# Mach_dieu_khien_tu_xa.net
KiCad netlist of a schematic drawn in Altium Designer
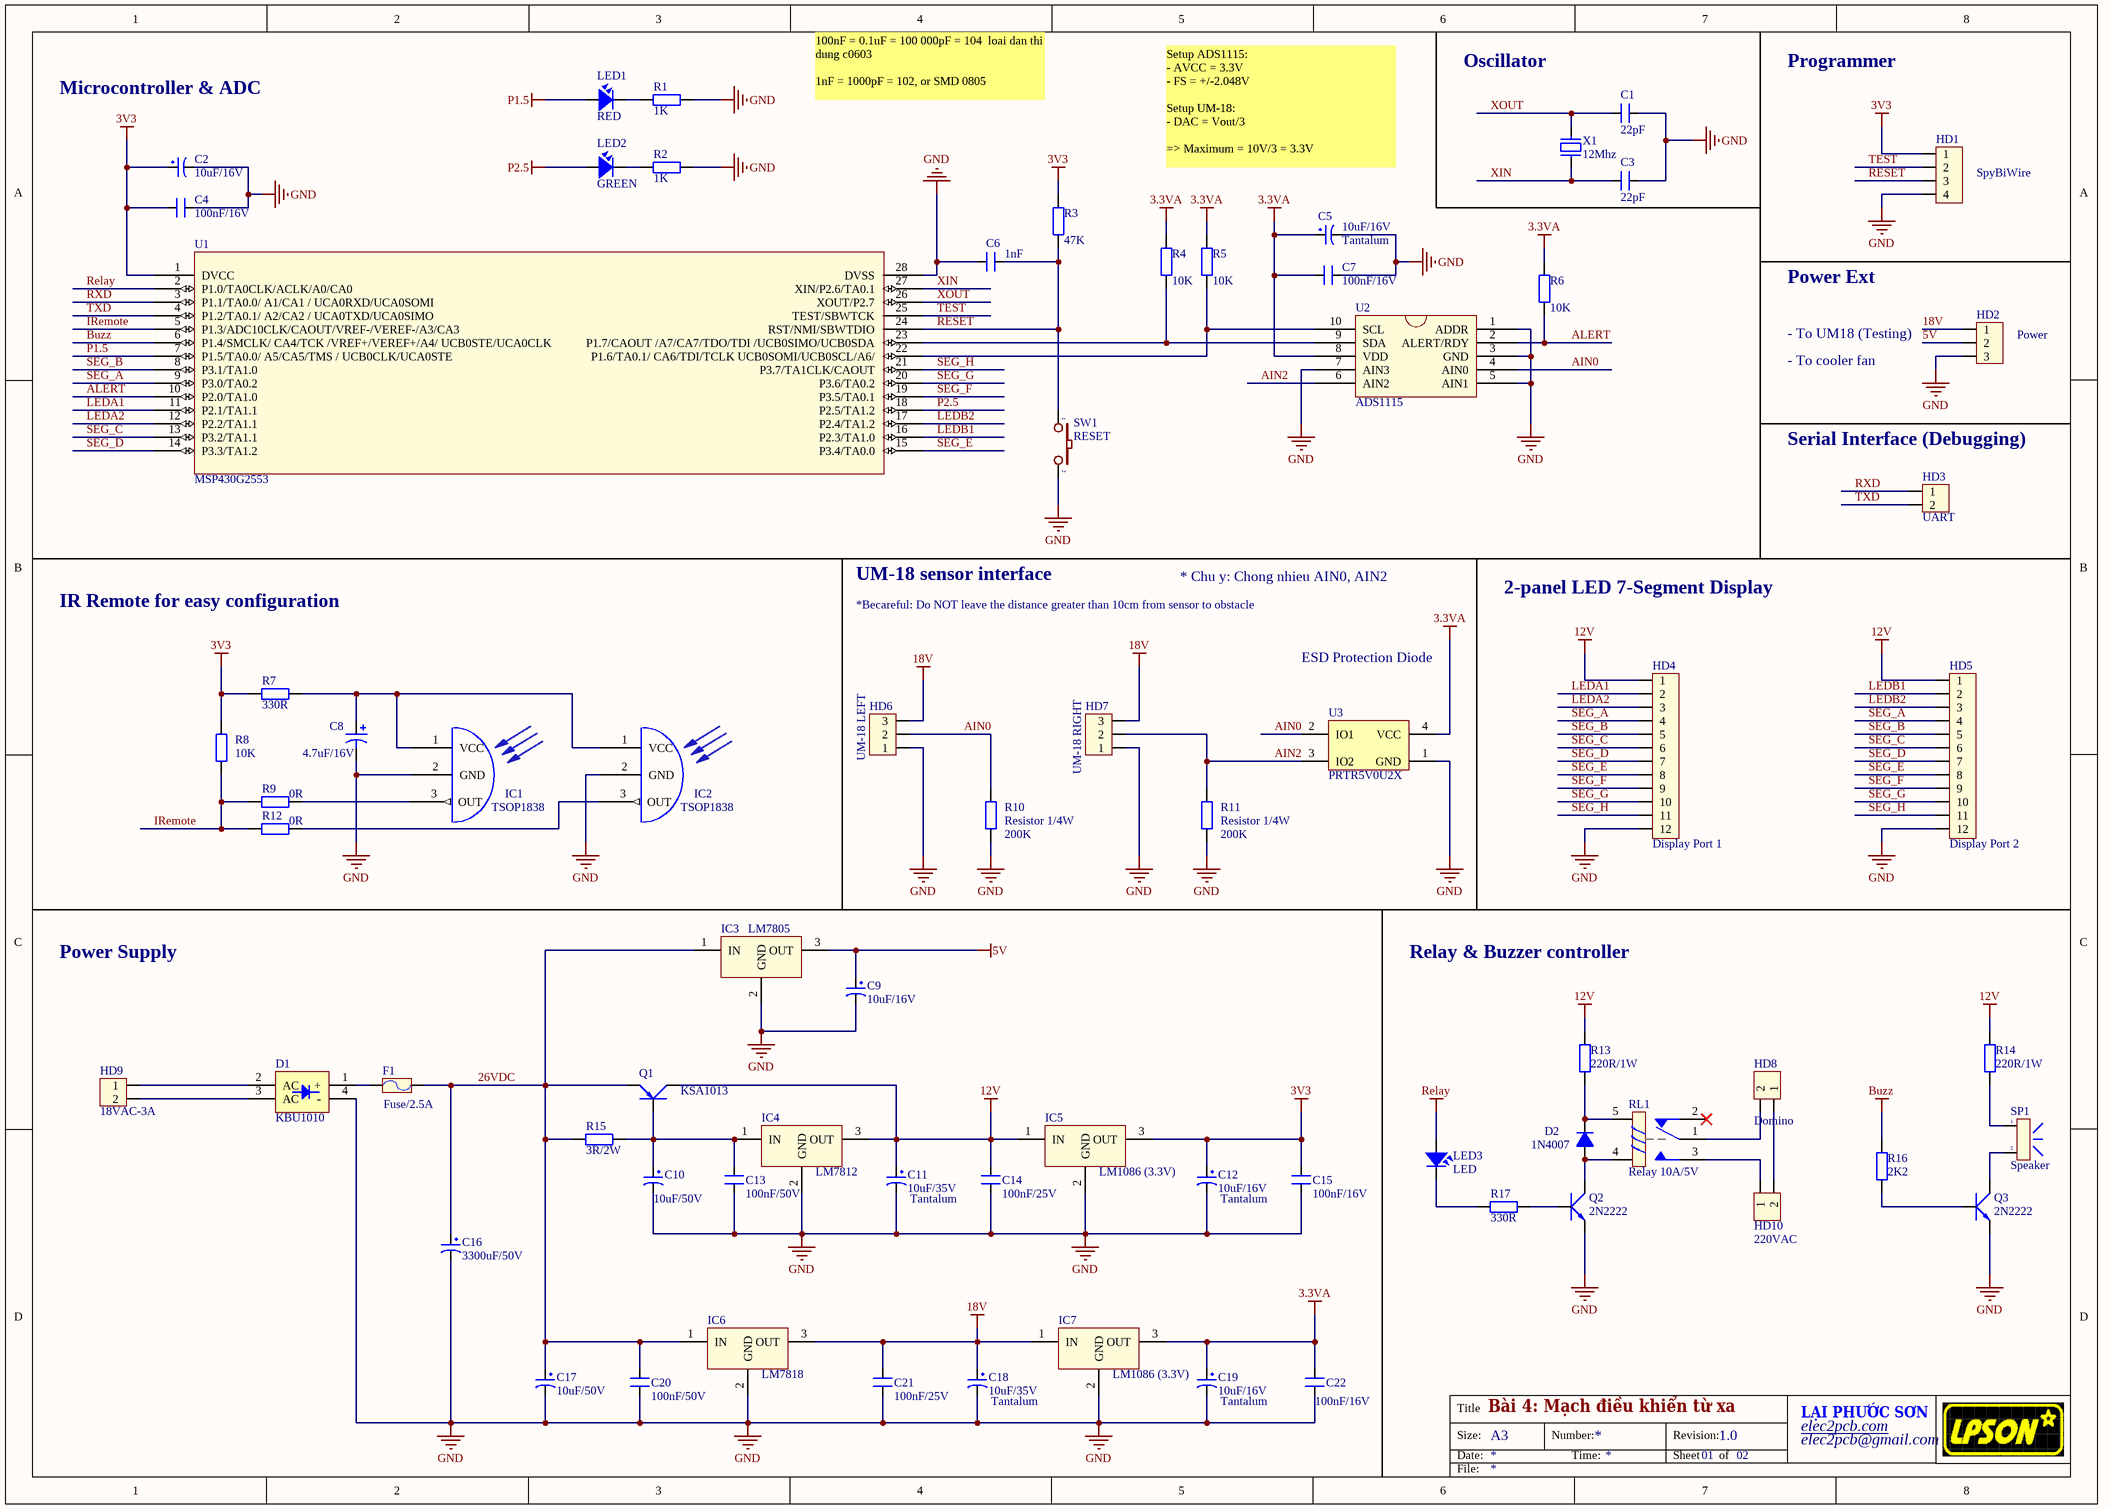
[diagram p0: Mach dieu khien tu xa.SchDoc]

(export (version "E")
  (design (tool "Eeschema 10.0.6"))
  (components
    (comp (ref "C1")
      (value "22pF")
      (footprint "C0603")
      (description "0805-SMD Capacitor")
      (libsource (lib "syhaunguyen") (part "CN1"))
    )
    (comp (ref "C2")
      (value "10uF/16V")
      (footprint "C0805")
      (description "Cap P  0,1uF < 22uF , 16 - 50V")
      (libsource (lib "") (part "CP1_1"))
    )
    (comp (ref "C3")
      (value "22pF")
      (footprint "C0603")
      (description "0805-SMD Capacitor")
      (libsource (lib "syhaunguyen") (part "CN1"))
    )
    (comp (ref "C4")
      (value "100nF/16V")
      (footprint "Tu gom 104")
      (description "Cap np 104 => 105pF")
      (libsource (lib "VNELEK") (part "CN2"))
    )
    (comp (ref "C5")
      (value "10uF/16V")
      (footprint "CAP_TANTA_10UF_16V")
      (description "Tantalum Capacitor")
      (fields (field (name "TYPE") "Tantalum"))
      (libsource (lib "") (part "CP1_1"))
    )
    (comp (ref "C6")
      (value "1nF")
      (footprint "C0805")
      (description "Cap np 104 => 105pF")
      (libsource (lib "VNELEK") (part "CN2"))
    )
    (comp (ref "C7")
      (value "100nF/16V")
      (footprint "Tu gom 104")
      (description "Cap np 104 => 105pF")
      (libsource (lib "VNELEK") (part "CN2"))
    )
    (comp (ref "C8")
      (value "4.7uF/16V")
      (footprint "C0805")
      (description "Polarized Capacitor (Radial)")
      (fields (field (name "Comment") "Cap Pol1") (field (name "PUBLISHER") "Altium Limited"))
      (libsource (lib "Miscellaneous Devices") (part "Cap Pol1"))
    )
    (comp (ref "C9")
      (value "10uF/16V")
      (footprint "CAP_10UF_16V")
      (description "Aluminium Capacitor")
      (libsource (lib "VNELEK") (part "CP1"))
    )
    (comp (ref "C10")
      (value "10uF/50V")
      (footprint "C_FC_10UF_50V")
      (description "Aluminium Capacitor")
      (libsource (lib "VNELEK") (part "CP1"))
    )
    (comp (ref "C11")
      (value "10uF/35V")
      (footprint "CAP_TANTA_10UF_35V")
      (description "Tantalum Capacitor")
      (fields (field (name "TYPE") "Tantalum"))
      (libsource (lib "VNELEK") (part "CP1"))
    )
    (comp (ref "C12")
      (value "10uF/16V")
      (footprint "CAP_TANTA_10UF_16V")
      (description "Tantalum Capacitor")
      (fields (field (name "TYPE") "Tantalum"))
      (libsource (lib "VNELEK") (part "CP1"))
    )
    (comp (ref "C13")
      (value "100nF/50V")
      (footprint "Tu gom 104")
      (description "Cap np 104 => 105pF")
      (libsource (lib "VNELEK") (part "CN2"))
    )
    (comp (ref "C14")
      (value "100nF/25V")
      (footprint "Tu gom 104")
      (description "Cap np 104 => 105pF")
      (libsource (lib "VNELEK") (part "CN2"))
    )
    (comp (ref "C15")
      (value "100nF/16V")
      (footprint "Tu gom 104")
      (description "Cap np 104 => 105pF")
      (libsource (lib "VNELEK") (part "CN2"))
    )
    (comp (ref "C16")
      (value "3300uF/50V")
      (footprint "CAP_3300UF_50V")
      (description "Cap P  0,1uF < 22uF , 16 - 50V")
      (libsource (lib "VNELEK") (part "CP1"))
    )
    (comp (ref "C17")
      (value "10uF/50V")
      (footprint "C_FC_10UF_50V")
      (description "Aluminium Capacitor")
      (libsource (lib "VNELEK") (part "CP1"))
    )
    (comp (ref "C18")
      (value "10uF/35V")
      (footprint "CAP_TANTA_10UF_35V")
      (description "Tantalum Capacitor")
      (fields (field (name "TYPE") "Tantalum"))
      (libsource (lib "VNELEK") (part "CP1"))
    )
    (comp (ref "C19")
      (value "10uF/16V")
      (footprint "CAP_TANTA_10UF_16V")
      (description "Tantalum Capacitor")
      (fields (field (name "TYPE") "Tantalum"))
      (libsource (lib "VNELEK") (part "CP1"))
    )
    (comp (ref "C20")
      (value "100nF/50V")
      (footprint "Tu gom 104")
      (description "Cap np 104 => 105pF")
      (libsource (lib "VNELEK") (part "CN2"))
    )
    (comp (ref "C21")
      (value "100nF/25V")
      (footprint "Tu gom 104")
      (description "Cap np 104 => 105pF")
      (libsource (lib "VNELEK") (part "CN2"))
    )
    (comp (ref "C22")
      (value "100nF/16V")
      (footprint "Tu gom 104")
      (description "Cap np 104 => 105pF")
      (libsource (lib "VNELEK") (part "CN2"))
    )
    (comp (ref "D1")
      (value "KBU1010")
      (footprint "KBU1010G")
      (description "10A glass passivated bridge rectifier")
      (libsource (lib "Tran Tuan") (part "KBU1010"))
    )
    (comp (ref "D2")
      (value "1N4007")
      (footprint "1N4007")
      (description "Diode 1A")
      (libsource (lib "VNELEK") (part "D1A"))
    )
    (comp (ref "F1")
      (value "Fuse/2.5A")
      (footprint "FUSE2_5A")
      (description "Fuse")
      (fields (field (name "DESIGNED BY") "VanDungEvn"))
      (libsource (lib "VNELEK") (part "Fuse"))
    )
    (comp (ref "HD1")
      (value "SpyBiWire")
      (footprint "Header_4")
      (description "Header 4 (Green)")
      (libsource (lib "VNELEK") (part "Hed4"))
    )
    (comp (ref "HD2")
      (value "Power")
      (footprint "CON3")
      (description "Header 3 (Green)")
      (libsource (lib "VNELEK") (part "Hed3"))
    )
    (comp (ref "HD3")
      (value "UART")
      (footprint "Header_2")
      (description "Header 2 (Green)")
      (libsource (lib "") (part "Hed2_1"))
    )
    (comp (ref "HD4")
      (value "Display Port 1")
      (footprint "CON12")
      (description "Header 12")
      (libsource (lib "Tran Tuan") (part "Hed12"))
    )
    (comp (ref "HD5")
      (value "Display Port 2")
      (footprint "CON12")
      (description "Header 12")
      (libsource (lib "Tran Tuan") (part "Hed12"))
    )
    (comp (ref "HD6")
      (value "UM-18 LEFT")
      (footprint "CON3")
      (description "Header 3 (Green)")
      (libsource (lib "") (part "Hed3_1"))
    )
    (comp (ref "HD7")
      (value "UM-18 RIGHT")
      (footprint "CON3")
      (description "Header 3 (Green)")
      (libsource (lib "") (part "Hed3_1"))
    )
    (comp (ref "HD8")
      (value "Domino")
      (footprint "DOMINO2_GREEN")
      (description "Header 2 (Green)")
      (libsource (lib "") (part "Hed2_1"))
    )
    (comp (ref "HD9")
      (value "18VAC-3A")
      (footprint "DOMINO2_GREEN")
      (description "Header 2 (Green)")
      (libsource (lib "") (part "Hed2_2"))
    )
    (comp (ref "HD10")
      (value "220VAC")
      (footprint "DOMINO2_GREEN")
      (description "Header 2 (Green)")
      (libsource (lib "VNELEK") (part "Hed2"))
    )
    (comp (ref "IC1")
      (value "TSOP1838")
      (footprint "TSOP1838")
      (libsource (lib "Tran Tuan") (part "TSOP1838"))
    )
    (comp (ref "IC2")
      (value "TSOP1838")
      (footprint "TSOP1838")
      (libsource (lib "Tran Tuan") (part "TSOP1838"))
    )
    (comp (ref "IC3")
      (value "LM7805")
      (footprint "LM7805")
      (description "Linear Regulator")
      (libsource (lib "VNELEK") (part "LM78xx"))
    )
    (comp (ref "IC4")
      (value "LM7812")
      (footprint "LM7805")
      (description "Linear Regulator")
      (fields (field (name "MANUFACTURER") "Fairchild Semiconductor"))
      (libsource (lib "VNELEK") (part "LM78xx"))
    )
    (comp (ref "IC5")
      (value "LM1086 (3.3V)")
      (footprint "LM1086")
      (description "Linear Regulator")
      (libsource (lib "VNELEK") (part "LM78xx"))
    )
    (comp (ref "IC6")
      (value "LM7818")
      (footprint "LM7805")
      (description "Linear Regulator")
      (libsource (lib "VNELEK") (part "LM78xx"))
    )
    (comp (ref "IC7")
      (value "LM1086 (3.3V)")
      (footprint "LM1086")
      (description "Linear Regulator")
      (libsource (lib "VNELEK") (part "LM78xx"))
    )
    (comp (ref "LED1")
      (value "RED")
      (footprint "LED3R")
      (description "LED Single colour Green and Red")
      (libsource (lib "VNELEK") (part "LED"))
    )
    (comp (ref "LED2")
      (value "GREEN")
      (footprint "LED3R")
      (description "LED Single colour Green and Red")
      (libsource (lib "VNELEK") (part "LED"))
    )
    (comp (ref "LED3")
      (value "LED")
      (footprint "LED3R")
      (description "LED Single colour Green and Red")
      (libsource (lib "VNELEK") (part "LED"))
    )
    (comp (ref "Q1")
      (value "KSA1013")
      (footprint "KSA1013")
      (description "PNP 600mW, ECB")
      (fields (field (name "MANUFACTURER") "Fairchild Semiconductor"))
      (libsource (lib "VNELEK") (part "A1015"))
    )
    (comp (ref "Q2")
      (value "2N2222")
      (footprint "2N2222")
      (description "TRANS GP SS NPN LP 40V TO92")
      (libsource (lib "VNELEK") (part "C1815"))
    )
    (comp (ref "Q3")
      (value "2N2222")
      (footprint "2N2222")
      (description "TRANS GP SS NPN LP 40V TO92")
      (libsource (lib "VNELEK") (part "C1815"))
    )
    (comp (ref "R1")
      (value "1K")
      (footprint "RESC2012(0805)")
      (description "Resistor")
      (fields (field (name "Comment") "Res2") (field (name "PUBLISHER") "Altium Limited"))
      (libsource (lib "") (part "Res2_1"))
    )
    (comp (ref "R2")
      (value "1K")
      (footprint "RESC2012(0805)")
      (description "Resistor")
      (fields (field (name "Comment") "Res2") (field (name "PUBLISHER") "Altium Limited"))
      (libsource (lib "") (part "Res2_1"))
    )
    (comp (ref "R3")
      (value "47K")
      (footprint "RESC2012(0805)")
      (description "Resistor")
      (fields (field (name "Comment") "Res2") (field (name "PUBLISHER") "Altium Limited"))
      (libsource (lib "Miscellaneous Devices") (part "Res2"))
    )
    (comp (ref "R4")
      (value "10K")
      (footprint "RESC2012(0805)")
      (description "Resistor")
      (fields (field (name "Comment") "Res2") (field (name "PUBLISHER") "Altium Limited"))
      (libsource (lib "Miscellaneous Devices") (part "Res2"))
    )
    (comp (ref "R5")
      (value "10K")
      (footprint "RESC2012(0805)")
      (description "Resistor")
      (fields (field (name "Comment") "Res2") (field (name "PUBLISHER") "Altium Limited"))
      (libsource (lib "Miscellaneous Devices") (part "Res2"))
    )
    (comp (ref "R6")
      (value "10K")
      (footprint "RESC2012(0805)")
      (description "Resistor")
      (fields (field (name "Comment") "Res2") (field (name "PUBLISHER") "Altium Limited"))
      (libsource (lib "Miscellaneous Devices") (part "Res2"))
    )
    (comp (ref "R7")
      (value "330R")
      (footprint "RESC2012(0805)")
      (description "Resistor")
      (fields (field (name "Comment") "Res2") (field (name "PUBLISHER") "Altium Limited"))
      (libsource (lib "") (part "Res2_1"))
    )
    (comp (ref "R8")
      (value "10K")
      (footprint "RESC2012(0805)")
      (description "Resistor")
      (fields (field (name "Comment") "Res2") (field (name "PUBLISHER") "Altium Limited"))
      (libsource (lib "Miscellaneous Devices") (part "Res2"))
    )
    (comp (ref "R9")
      (value "0R")
      (footprint "RESC2012(0805)")
      (description "Resistor")
      (fields (field (name "Comment") "Res2") (field (name "PUBLISHER") "Altium Limited"))
      (libsource (lib "") (part "Res2_1"))
    )
    (comp (ref "R10")
      (value "Resistor 1/4W")
      (footprint "RESC2012(0805)")
      (fields (field (name "ALTIUM_VALUE") "200K"))
      (libsource (lib "") (part "Res2_2"))
    )
    (comp (ref "R11")
      (value "Resistor 1/4W")
      (footprint "RESC2012(0805)")
      (fields (field (name "ALTIUM_VALUE") "200K"))
      (libsource (lib "") (part "Res2_2"))
    )
    (comp (ref "R12")
      (value "0R")
      (footprint "RESC2012(0805)")
      (description "Resistor")
      (fields (field (name "Comment") "Res2") (field (name "PUBLISHER") "Altium Limited"))
      (libsource (lib "") (part "Res2_1"))
    )
    (comp (ref "R13")
      (value "220R/1W")
      (footprint "CFR1WS")
      (description "Resistor")
      (fields (field (name "Comment") "Res2") (field (name "PUBLISHER") "Altium Limited"))
      (libsource (lib "") (part "Res2_2"))
    )
    (comp (ref "R14")
      (value "220R/1W")
      (footprint "CFR1WS")
      (description "Resistor")
      (fields (field (name "Comment") "Res2") (field (name "PUBLISHER") "Altium Limited"))
      (libsource (lib "") (part "Res2_2"))
    )
    (comp (ref "R15")
      (value "3R/2W")
      (footprint "R2WD")
      (description "Resistor")
      (fields (field (name "Comment") "Res2") (field (name "PUBLISHER") "Altium Limited"))
      (libsource (lib "") (part "Res2_1"))
    )
    (comp (ref "R16")
      (value "2K2")
      (footprint "RES 1/4W CFR25")
      (description "Resistor")
      (fields (field (name "Comment") "Res2") (field (name "PUBLISHER") "Altium Limited"))
      (libsource (lib "") (part "Res2_2"))
    )
    (comp (ref "R17")
      (value "330R")
      (footprint "RES 1/4W CFR25")
      (description "Resistor")
      (fields (field (name "Comment") "Res2") (field (name "PUBLISHER") "Altium Limited"))
      (libsource (lib "") (part "Res2_1"))
    )
    (comp (ref "RL1")
      (value "Relay 10A/5V")
      (footprint "RL_10A_5V")
      (description "Relay SPDT,10A - 12VDC 5 Pin")
      (libsource (lib "VNELEK") (part "Relay 1"))
    )
    (comp (ref "SP1")
      (value "Speaker")
      (footprint "SPEAKER")
      (description "Speaker Chip")
      (libsource (lib "VNELEK") (part "SPK"))
    )
    (comp (ref "SW1")
      (value "RESET")
      (footprint "BUTTON 2PIN TRON")
      (description "Switch button 2 pin")
      (libsource (lib "VNELEK") (part "SW2"))
    )
    (comp (ref "U1")
      (value "MSP430G2553")
      (footprint "MSP430G2253IPW28R")
      (description "MSP430G2553 (28 pins)")
      (libsource (lib "Tran Tuan") (part "MSP430G2553"))
    )
    (comp (ref "U2")
      (value "ADS1115")
      (footprint "ADS1115")
      (description "Analog to Digital Converter")
      (libsource (lib "Tran Tuan") (part "ADS1115"))
    )
    (comp (ref "U3")
      (value "PRTR5V0U2X")
      (footprint "PRTR5V0U2X")
      (description "ESD protection diode")
      (libsource (lib "Tran Tuan") (part "PRTR5V0U2X"))
    )
    (comp (ref "X1")
      (value "12Mhz")
      (footprint "CRYSTAL")
      (description "Crystal For all Crystal 2pin.")
      (libsource (lib "syhaunguyen") (part "XT2"))
    )
  )
  (nets
    (net (code "1") (name "/26VDC") (class "Default")
      (node (ref "C16") (pin "1") (pinfunction "1_1") (pintype "passive"))
      (node (ref "C17") (pin "1") (pinfunction "1_1") (pintype "passive"))
      (node (ref "C20") (pin "2") (pinfunction "2_2") (pintype "passive"))
      (node (ref "F1") (pin "2") (pinfunction "2_2") (pintype "passive"))
      (node (ref "IC3") (pin "1") (pinfunction "IN_1") (pintype "passive"))
      (node (ref "IC6") (pin "1") (pinfunction "IN_1") (pintype "passive"))
      (node (ref "Q1") (pin "1") (pinfunction "E_1") (pintype "passive"))
      (node (ref "R15") (pin "2") (pinfunction "2_2") (pintype "passive"))
    )
    (net (code "2") (name "/AIN0") (class "Default")
      (node (ref "HD6") (pin "2") (pinfunction "2_2") (pintype "passive"))
      (node (ref "R10") (pin "1") (pinfunction "1_1") (pintype "passive"))
      (node (ref "U2") (pin "4") (pinfunction "AIN0_4") (pintype "passive"))
      (node (ref "U3") (pin "2") (pinfunction "IO1_2") (pintype "passive"))
    )
    (net (code "3") (name "/AIN2") (class "Default")
      (node (ref "HD7") (pin "2") (pinfunction "2_2") (pintype "passive"))
      (node (ref "R11") (pin "1") (pinfunction "1_1") (pintype "passive"))
      (node (ref "U2") (pin "6") (pinfunction "AIN2_6") (pintype "passive"))
      (node (ref "U3") (pin "3") (pinfunction "IO2_3") (pintype "passive"))
    )
    (net (code "4") (name "/ALERT") (class "Default")
      (node (ref "R6") (pin "1") (pinfunction "1_1") (pintype "passive"))
      (node (ref "U1") (pin "10") (pinfunction "P2.0/TA1.0_10") (pintype "bidirectional"))
      (node (ref "U2") (pin "2") (pinfunction "ALERT/RDY_2") (pintype "passive"))
    )
    (net (code "5") (name "/IRemote") (class "Default")
      (node (ref "R12") (pin "2") (pinfunction "2_2") (pintype "passive"))
      (node (ref "R8") (pin "1") (pinfunction "1_1") (pintype "passive"))
      (node (ref "R9") (pin "2") (pinfunction "2_2") (pintype "passive"))
      (node (ref "U1") (pin "5") (pinfunction "P1.3/ADC10CLK/CAOUT/VREF-/VEREF-/A3/CA3_5") (pintype "bidirectional"))
    )
    (net (code "6") (name "/LEDA1") (class "Default")
      (node (ref "HD4") (pin "2") (pinfunction "2_2") (pintype "passive"))
      (node (ref "U1") (pin "11") (pinfunction "P2.1/TA1.1_11") (pintype "bidirectional"))
    )
    (net (code "7") (name "/LEDA2") (class "Default")
      (node (ref "HD4") (pin "3") (pinfunction "3_3") (pintype "passive"))
      (node (ref "U1") (pin "12") (pinfunction "P2.2/TA1.1_12") (pintype "bidirectional"))
    )
    (net (code "8") (name "/LEDB1") (class "Default")
      (node (ref "HD5") (pin "2") (pinfunction "2_2") (pintype "passive"))
      (node (ref "U1") (pin "16") (pinfunction "P2.3/TA1.0_16") (pintype "bidirectional"))
    )
    (net (code "9") (name "/LEDB2") (class "Default")
      (node (ref "HD5") (pin "3") (pinfunction "3_3") (pintype "passive"))
      (node (ref "U1") (pin "17") (pinfunction "P2.4/TA1.2_17") (pintype "bidirectional"))
    )
    (net (code "10") (name "/RESET") (class "Default")
      (node (ref "C6") (pin "2") (pinfunction "2_2") (pintype "passive"))
      (node (ref "HD1") (pin "3") (pinfunction "3_3") (pintype "passive"))
      (node (ref "R3") (pin "1") (pinfunction "1_1") (pintype "passive"))
      (node (ref "SW1") (pin "1") (pinfunction "1_1") (pintype "passive"))
      (node (ref "U1") (pin "24") (pinfunction "RST/NMI/SBWTDIO_24") (pintype "passive"))
    )
    (net (code "11") (name "/RXD") (class "Default")
      (node (ref "HD3") (pin "1") (pinfunction "1_1") (pintype "passive"))
      (node (ref "U1") (pin "3") (pinfunction "P1.1/TA0.0/_A1/CA1_/_UCA0RXD/UCA0SOMI_3") (pintype "bidirectional"))
    )
    (net (code "12") (name "/SEG_A") (class "Default")
      (node (ref "HD4") (pin "4") (pinfunction "4_4") (pintype "passive"))
      (node (ref "HD5") (pin "4") (pinfunction "4_4") (pintype "passive"))
      (node (ref "U1") (pin "9") (pinfunction "P3.0/TA0.2_9") (pintype "bidirectional"))
    )
    (net (code "13") (name "/SEG_B") (class "Default")
      (node (ref "HD4") (pin "5") (pinfunction "5_5") (pintype "passive"))
      (node (ref "HD5") (pin "5") (pinfunction "5_5") (pintype "passive"))
      (node (ref "U1") (pin "8") (pinfunction "P3.1/TA1.0_8") (pintype "bidirectional"))
    )
    (net (code "14") (name "/SEG_C") (class "Default")
      (node (ref "HD4") (pin "6") (pinfunction "6_6") (pintype "passive"))
      (node (ref "HD5") (pin "6") (pinfunction "6_6") (pintype "passive"))
      (node (ref "U1") (pin "13") (pinfunction "P3.2/TA1.1_13") (pintype "bidirectional"))
    )
    (net (code "15") (name "/SEG_D") (class "Default")
      (node (ref "HD4") (pin "7") (pinfunction "7_7") (pintype "passive"))
      (node (ref "HD5") (pin "7") (pinfunction "7_7") (pintype "passive"))
      (node (ref "U1") (pin "14") (pinfunction "P3.3/TA1.2_14") (pintype "bidirectional"))
    )
    (net (code "16") (name "/SEG_E") (class "Default")
      (node (ref "HD4") (pin "8") (pinfunction "8_8") (pintype "passive"))
      (node (ref "HD5") (pin "8") (pinfunction "8_8") (pintype "passive"))
      (node (ref "U1") (pin "15") (pinfunction "P3.4/TA0.0_15") (pintype "bidirectional"))
    )
    (net (code "17") (name "/SEG_F") (class "Default")
      (node (ref "HD4") (pin "9") (pinfunction "9_9") (pintype "passive"))
      (node (ref "HD5") (pin "9") (pinfunction "9_9") (pintype "passive"))
      (node (ref "U1") (pin "19") (pinfunction "P3.5/TA0.1_19") (pintype "bidirectional"))
    )
    (net (code "18") (name "/SEG_G") (class "Default")
      (node (ref "HD4") (pin "10") (pinfunction "10_10") (pintype "passive"))
      (node (ref "HD5") (pin "10") (pinfunction "10_10") (pintype "passive"))
      (node (ref "U1") (pin "20") (pinfunction "P3.6/TA0.2_20") (pintype "bidirectional"))
    )
    (net (code "19") (name "/SEG_H") (class "Default")
      (node (ref "HD4") (pin "11") (pinfunction "11_11") (pintype "passive"))
      (node (ref "HD5") (pin "11") (pinfunction "11_11") (pintype "passive"))
      (node (ref "U1") (pin "21") (pinfunction "P3.7/TA1CLK/CAOUT_21") (pintype "bidirectional"))
    )
    (net (code "20") (name "/TEST") (class "Default")
      (node (ref "HD1") (pin "2") (pinfunction "2_2") (pintype "passive"))
      (node (ref "U1") (pin "25") (pinfunction "TEST/SBWTCK_25") (pintype "passive"))
    )
    (net (code "21") (name "/TXD") (class "Default")
      (node (ref "HD3") (pin "2") (pinfunction "2_2") (pintype "passive"))
      (node (ref "U1") (pin "4") (pinfunction "P1.2/TA0.1/_A2/CA2_/_UCA0TXD/UCA0SIMO_4") (pintype "bidirectional"))
    )
    (net (code "22") (name "/XIN") (class "Default")
      (node (ref "C3") (pin "2") (pinfunction "2_2") (pintype "passive"))
      (node (ref "U1") (pin "27") (pinfunction "XIN/P2.6/TA0.1_27") (pintype "bidirectional"))
      (node (ref "X1") (pin "2") (pinfunction "2_2") (pintype "passive"))
    )
    (net (code "23") (name "/XOUT") (class "Default")
      (node (ref "C1") (pin "2") (pinfunction "2_2") (pintype "passive"))
      (node (ref "U1") (pin "26") (pinfunction "XOUT/P2.7_26") (pintype "bidirectional"))
      (node (ref "X1") (pin "1") (pinfunction "1_1") (pintype "passive"))
    )
    (net (code "24") (name "3.3VA") (class "Default")
      (node (ref "C19") (pin "1") (pinfunction "1_1") (pintype "passive"))
      (node (ref "C22") (pin "2") (pinfunction "2_2") (pintype "passive"))
      (node (ref "C5") (pin "1") (pinfunction "1_1") (pintype "passive"))
      (node (ref "C7") (pin "2") (pinfunction "2_2") (pintype "passive"))
      (node (ref "IC7") (pin "3") (pinfunction "OUT_3") (pintype "passive"))
      (node (ref "R4") (pin "2") (pinfunction "2_2") (pintype "passive"))
      (node (ref "R5") (pin "2") (pinfunction "2_2") (pintype "passive"))
      (node (ref "R6") (pin "2") (pinfunction "2_2") (pintype "passive"))
      (node (ref "U2") (pin "8") (pinfunction "VDD_8") (pintype "passive"))
      (node (ref "U3") (pin "4") (pinfunction "VCC_4") (pintype "passive"))
    )
    (net (code "25") (name "3V3") (class "Default")
      (node (ref "C12") (pin "1") (pinfunction "1_1") (pintype "passive"))
      (node (ref "C15") (pin "2") (pinfunction "2_2") (pintype "passive"))
      (node (ref "C2") (pin "1") (pinfunction "1_1") (pintype "passive"))
      (node (ref "C4") (pin "2") (pinfunction "2_2") (pintype "passive"))
      (node (ref "HD1") (pin "1") (pinfunction "1_1") (pintype "passive"))
      (node (ref "IC5") (pin "3") (pinfunction "OUT_3") (pintype "passive"))
      (node (ref "R3") (pin "2") (pinfunction "2_2") (pintype "passive"))
      (node (ref "R7") (pin "2") (pinfunction "2_2") (pintype "passive"))
      (node (ref "R8") (pin "2") (pinfunction "2_2") (pintype "passive"))
      (node (ref "U1") (pin "1") (pinfunction "DVCC_1") (pintype "power_in"))
    )
    (net (code "26") (name "5V") (class "Default")
      (node (ref "C9") (pin "1") (pinfunction "1_1") (pintype "passive"))
      (node (ref "HD2") (pin "2") (pinfunction "2_2") (pintype "passive"))
      (node (ref "IC3") (pin "3") (pinfunction "OUT_3") (pintype "passive"))
    )
    (net (code "27") (name "12V") (class "Default")
      (node (ref "C11") (pin "1") (pinfunction "1_1") (pintype "passive"))
      (node (ref "C14") (pin "2") (pinfunction "2_2") (pintype "passive"))
      (node (ref "HD4") (pin "1") (pinfunction "1_1") (pintype "passive"))
      (node (ref "HD5") (pin "1") (pinfunction "1_1") (pintype "passive"))
      (node (ref "IC4") (pin "3") (pinfunction "OUT_3") (pintype "passive"))
      (node (ref "IC5") (pin "1") (pinfunction "IN_1") (pintype "passive"))
      (node (ref "Q1") (pin "2") (pinfunction "C_2") (pintype "passive"))
      (node (ref "R13") (pin "1") (pinfunction "1_1") (pintype "passive"))
      (node (ref "R14") (pin "1") (pinfunction "1_1") (pintype "passive"))
    )
    (net (code "28") (name "18V") (class "Default")
      (node (ref "C18") (pin "1") (pinfunction "1_1") (pintype "passive"))
      (node (ref "C21") (pin "2") (pinfunction "2_2") (pintype "passive"))
      (node (ref "HD2") (pin "1") (pinfunction "1_1") (pintype "passive"))
      (node (ref "HD6") (pin "3") (pinfunction "3_3") (pintype "passive"))
      (node (ref "HD7") (pin "3") (pinfunction "3_3") (pintype "passive"))
      (node (ref "IC6") (pin "3") (pinfunction "OUT_3") (pintype "passive"))
      (node (ref "IC7") (pin "1") (pinfunction "IN_1") (pintype "passive"))
    )
    (net (code "29") (name "Buzz") (class "Default")
      (node (ref "R16") (pin "1") (pinfunction "1_1") (pintype "passive"))
      (node (ref "U1") (pin "6") (pinfunction "P1.4/SMCLK/_CA4/TCK_/VREF+/VEREF+/A4/_UCB0STE/UCA0CLK_6") (pintype "bidirectional"))
    )
    (net (code "30") (name "GND") (class "Default")
      (node (ref "C1") (pin "1") (pinfunction "1_1") (pintype "passive"))
      (node (ref "C10") (pin "2") (pinfunction "2_2") (pintype "passive"))
      (node (ref "C11") (pin "2") (pinfunction "2_2") (pintype "passive"))
      (node (ref "C12") (pin "2") (pinfunction "2_2") (pintype "passive"))
      (node (ref "C13") (pin "1") (pinfunction "1_1") (pintype "passive"))
      (node (ref "C14") (pin "1") (pinfunction "1_1") (pintype "passive"))
      (node (ref "C15") (pin "1") (pinfunction "1_1") (pintype "passive"))
      (node (ref "C16") (pin "2") (pinfunction "2_2") (pintype "passive"))
      (node (ref "C17") (pin "2") (pinfunction "2_2") (pintype "passive"))
      (node (ref "C18") (pin "2") (pinfunction "2_2") (pintype "passive"))
      (node (ref "C19") (pin "2") (pinfunction "2_2") (pintype "passive"))
      (node (ref "C2") (pin "2") (pinfunction "2_2") (pintype "passive"))
      (node (ref "C20") (pin "1") (pinfunction "1_1") (pintype "passive"))
      (node (ref "C21") (pin "1") (pinfunction "1_1") (pintype "passive"))
      (node (ref "C22") (pin "1") (pinfunction "1_1") (pintype "passive"))
      (node (ref "C3") (pin "1") (pinfunction "1_1") (pintype "passive"))
      (node (ref "C4") (pin "1") (pinfunction "1_1") (pintype "passive"))
      (node (ref "C5") (pin "2") (pinfunction "2_2") (pintype "passive"))
      (node (ref "C6") (pin "1") (pinfunction "1_1") (pintype "passive"))
      (node (ref "C7") (pin "1") (pinfunction "1_1") (pintype "passive"))
      (node (ref "C8") (pin "2") (pinfunction "2_2") (pintype "passive"))
      (node (ref "C9") (pin "2") (pinfunction "2_2") (pintype "passive"))
      (node (ref "D1") (pin "4") (pinfunction "-_4") (pintype "power_in"))
      (node (ref "HD1") (pin "4") (pinfunction "4_4") (pintype "passive"))
      (node (ref "HD2") (pin "3") (pinfunction "3_3") (pintype "passive"))
      (node (ref "HD4") (pin "12") (pinfunction "12_12") (pintype "passive"))
      (node (ref "HD5") (pin "12") (pinfunction "12_12") (pintype "passive"))
      (node (ref "HD6") (pin "1") (pinfunction "1_1") (pintype "passive"))
      (node (ref "HD7") (pin "1") (pinfunction "1_1") (pintype "passive"))
      (node (ref "IC1") (pin "2") (pinfunction "GND_2") (pintype "power_in"))
      (node (ref "IC2") (pin "2") (pinfunction "GND_2") (pintype "power_in"))
      (node (ref "IC3") (pin "2") (pinfunction "GND_2") (pintype "passive"))
      (node (ref "IC4") (pin "2") (pinfunction "GND_2") (pintype "passive"))
      (node (ref "IC5") (pin "2") (pinfunction "GND_2") (pintype "passive"))
      (node (ref "IC6") (pin "2") (pinfunction "GND_2") (pintype "passive"))
      (node (ref "IC7") (pin "2") (pinfunction "GND_2") (pintype "passive"))
      (node (ref "Q2") (pin "1") (pinfunction "E_1") (pintype "passive"))
      (node (ref "Q3") (pin "1") (pinfunction "E_1") (pintype "passive"))
      (node (ref "R1") (pin "1") (pinfunction "1_1") (pintype "passive"))
      (node (ref "R10") (pin "2") (pinfunction "2_2") (pintype "passive"))
      (node (ref "R11") (pin "2") (pinfunction "2_2") (pintype "passive"))
      (node (ref "R2") (pin "1") (pinfunction "1_1") (pintype "passive"))
      (node (ref "SW1") (pin "2") (pinfunction "2_2") (pintype "passive"))
      (node (ref "U1") (pin "28") (pinfunction "DVSS_28") (pintype "passive"))
      (node (ref "U2") (pin "1") (pinfunction "ADDR_1") (pintype "passive"))
      (node (ref "U2") (pin "3") (pinfunction "GND_3") (pintype "passive"))
      (node (ref "U2") (pin "5") (pinfunction "AIN1_5") (pintype "passive"))
      (node (ref "U2") (pin "7") (pinfunction "AIN3_7") (pintype "passive"))
      (node (ref "U3") (pin "1") (pinfunction "GND_1") (pintype "passive"))
    )
    (net (code "31") (name "Net-(D1-+)") (class "Default")
      (node (ref "D1") (pin "1") (pinfunction "+_1") (pintype "power_in"))
      (node (ref "F1") (pin "1") (pinfunction "1_1") (pintype "passive"))
    )
    (net (code "32") (name "Net-(D1-AC-Pad2)") (class "Default")
      (node (ref "D1") (pin "2") (pinfunction "AC_2") (pintype "power_in"))
      (node (ref "HD9") (pin "1") (pinfunction "1_1") (pintype "passive"))
    )
    (net (code "33") (name "Net-(D1-AC-Pad3)") (class "Default")
      (node (ref "D1") (pin "3") (pinfunction "AC_3") (pintype "power_in"))
      (node (ref "HD9") (pin "2") (pinfunction "2_2") (pintype "passive"))
    )
    (net (code "34") (name "Net-(D2-A)") (class "Default")
      (node (ref "D2") (pin "1") (pinfunction "A_1") (pintype "passive"))
      (node (ref "Q2") (pin "3") (pinfunction "C_3") (pintype "passive"))
      (node (ref "RL1") (pin "4") (pinfunction "4_4") (pintype "passive"))
    )
    (net (code "35") (name "Net-(D2-K)") (class "Default")
      (node (ref "D2") (pin "2") (pinfunction "K_2") (pintype "passive"))
      (node (ref "R13") (pin "2") (pinfunction "2_2") (pintype "passive"))
      (node (ref "RL1") (pin "5") (pinfunction "5_5") (pintype "passive"))
    )
    (net (code "36") (name "Net-(HD8-Pad2)") (class "Default")
      (node (ref "HD8") (pin "2") (pinfunction "2_2") (pintype "passive"))
      (node (ref "RL1") (pin "1") (pinfunction "1_1") (pintype "passive"))
    )
    (net (code "37") (name "Net-(HD10-Pad1)") (class "Default")
      (node (ref "HD10") (pin "1") (pinfunction "1_1") (pintype "passive"))
      (node (ref "RL1") (pin "3") (pinfunction "3_3") (pintype "passive"))
    )
    (net (code "38") (name "Net-(HD10-Pad2)") (class "Default")
      (node (ref "HD10") (pin "2") (pinfunction "2_2") (pintype "passive"))
      (node (ref "HD8") (pin "1") (pinfunction "1_1") (pintype "passive"))
    )
    (net (code "39") (name "Net-(IC1-OUT)") (class "Default")
      (node (ref "IC1") (pin "3") (pinfunction "OUT_3") (pintype "output"))
      (node (ref "R9") (pin "1") (pinfunction "1_1") (pintype "passive"))
    )
    (net (code "40") (name "Net-(IC1-VCC)") (class "Default")
      (node (ref "C8") (pin "1") (pinfunction "1_1") (pintype "passive"))
      (node (ref "IC1") (pin "1") (pinfunction "VCC_1") (pintype "power_in"))
      (node (ref "IC2") (pin "1") (pinfunction "VCC_1") (pintype "power_in"))
      (node (ref "R7") (pin "1") (pinfunction "1_1") (pintype "passive"))
    )
    (net (code "41") (name "Net-(IC2-OUT)") (class "Default")
      (node (ref "IC2") (pin "3") (pinfunction "OUT_3") (pintype "output"))
      (node (ref "R12") (pin "1") (pinfunction "1_1") (pintype "passive"))
    )
    (net (code "42") (name "Net-(IC4-IN)") (class "Default")
      (node (ref "C10") (pin "1") (pinfunction "1_1") (pintype "passive"))
      (node (ref "C13") (pin "2") (pinfunction "2_2") (pintype "passive"))
      (node (ref "IC4") (pin "1") (pinfunction "IN_1") (pintype "passive"))
      (node (ref "Q1") (pin "3") (pinfunction "B_3") (pintype "passive"))
      (node (ref "R15") (pin "1") (pinfunction "1_1") (pintype "passive"))
    )
    (net (code "43") (name "Net-(LED1-Pad2)") (class "Default")
      (node (ref "LED1") (pin "2") (pinfunction "2_2") (pintype "passive"))
      (node (ref "R1") (pin "2") (pinfunction "2_2") (pintype "passive"))
    )
    (net (code "44") (name "Net-(LED2-Pad2)") (class "Default")
      (node (ref "LED2") (pin "2") (pinfunction "2_2") (pintype "passive"))
      (node (ref "R2") (pin "2") (pinfunction "2_2") (pintype "passive"))
    )
    (net (code "45") (name "Net-(LED3-Pad2)") (class "Default")
      (node (ref "LED3") (pin "2") (pinfunction "2_2") (pintype "passive"))
      (node (ref "R17") (pin "2") (pinfunction "2_2") (pintype "passive"))
    )
    (net (code "46") (name "Net-(Q2-B)") (class "Default")
      (node (ref "Q2") (pin "2") (pinfunction "B_2") (pintype "passive"))
      (node (ref "R17") (pin "1") (pinfunction "1_1") (pintype "passive"))
    )
    (net (code "47") (name "Net-(Q3-B)") (class "Default")
      (node (ref "Q3") (pin "2") (pinfunction "B_2") (pintype "passive"))
      (node (ref "R16") (pin "2") (pinfunction "2_2") (pintype "passive"))
    )
    (net (code "48") (name "Net-(Q3-C)") (class "Default")
      (node (ref "Q3") (pin "3") (pinfunction "C_3") (pintype "passive"))
      (node (ref "SP1") (pin "2") (pinfunction "2_2") (pintype "passive"))
    )
    (net (code "49") (name "Net-(R14-Pad2)") (class "Default")
      (node (ref "R14") (pin "2") (pinfunction "2_2") (pintype "passive"))
      (node (ref "SP1") (pin "1") (pinfunction "1_1") (pintype "passive"))
    )
    (net (code "50") (name "Net-(U1-P1.6{slash}TA0.1{slash}_CA6{slash}TDI{slash}TCLK_UCB0SOMI{slash}UCB0SCL{slash}A6{slash})") (class "Default")
      (node (ref "R5") (pin "1") (pinfunction "1_1") (pintype "passive"))
      (node (ref "U1") (pin "22") (pinfunction "P1.6/TA0.1/_CA6/TDI/TCLK_UCB0SOMI/UCB0SCL/A6/_22") (pintype "bidirectional"))
      (node (ref "U2") (pin "10") (pinfunction "SCL_10") (pintype "passive"))
    )
    (net (code "51") (name "Net-(U1-P1.7{slash}CAOUT_{slash}A7{slash}CA7{slash}TDO{slash}TDI_{slash}UCB0SIMO{slash}UCB0SDA)") (class "Default")
      (node (ref "R4") (pin "1") (pinfunction "1_1") (pintype "passive"))
      (node (ref "U1") (pin "23") (pinfunction "P1.7/CAOUT_/A7/CA7/TDO/TDI_/UCB0SIMO/UCB0SDA_23") (pintype "bidirectional"))
      (node (ref "U2") (pin "9") (pinfunction "SDA_9") (pintype "passive"))
    )
    (net (code "52") (name "P1.5") (class "Default")
      (node (ref "LED1") (pin "1") (pinfunction "1_1") (pintype "passive"))
      (node (ref "U1") (pin "7") (pinfunction "P1.5/TA0.0/_A5/CA5/TMS_/_UCB0CLK/UCA0STE_7") (pintype "bidirectional"))
    )
    (net (code "53") (name "P2.5") (class "Default")
      (node (ref "LED2") (pin "1") (pinfunction "1_1") (pintype "passive"))
      (node (ref "U1") (pin "18") (pinfunction "P2.5/TA1.2_18") (pintype "bidirectional"))
    )
    (net (code "54") (name "Relay") (class "Default")
      (node (ref "LED3") (pin "1") (pinfunction "1_1") (pintype "passive"))
      (node (ref "U1") (pin "2") (pinfunction "P1.0/TA0CLK/ACLK/A0/CA0_2") (pintype "bidirectional"))
    )
    (net (code "55") (name "unconnected-(RL1-Pad2)") (class "Default")
      (node (ref "RL1") (pin "2") (pinfunction "2_2") (pintype "passive+no_connect"))
    )
  )
)
